# kitchenClock_v3.net
KiCad netlist of a schematic drawn in EAGLE
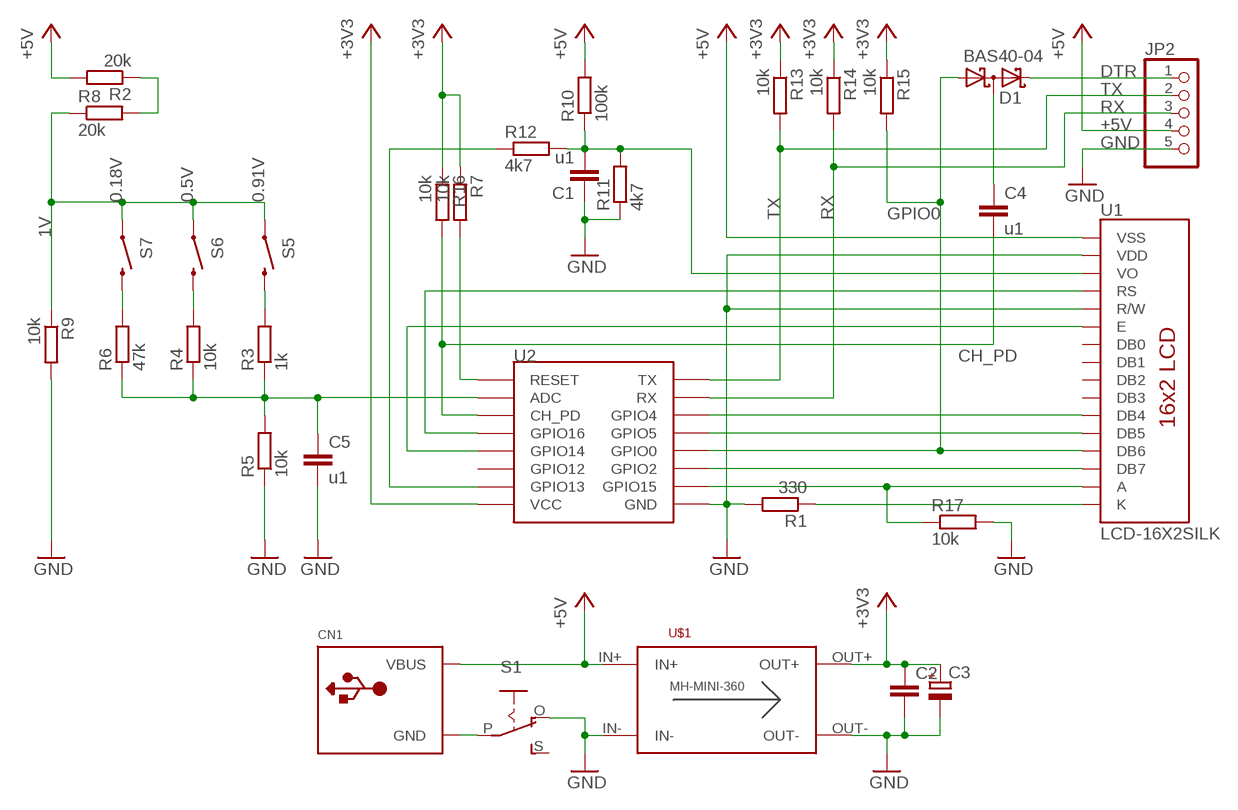
[diagram p0: schematic, sheet 1]

(export (version "E")
  (design (tool "Eeschema 10.0.6"))
  (components
    (comp (ref "C1")
      (value "u1")
      (footprint "eagle-import:C075-032X103")
      (libsource (lib "eagle-import") (part "C-EU075-032X103"))
    )
    (comp (ref "C2")
      (value "C-EU025-025X050")
      (footprint "eagle-import:C025-025X050")
      (libsource (lib "eagle-import") (part "C-EU025-025X050"))
    )
    (comp (ref "C3")
      (value "CPOL-EUTT2D5L")
      (footprint "eagle-import:TT2D5L")
      (libsource (lib "eagle-import") (part "CPOL-EUTT2D5L"))
    )
    (comp (ref "C4")
      (value "u1")
      (footprint "eagle-import:C075-032X103")
      (libsource (lib "eagle-import") (part "C-EU075-032X103"))
    )
    (comp (ref "C5")
      (value "u1")
      (footprint "eagle-import:C025-025X050")
      (libsource (lib "eagle-import") (part "C-EU025-025X050"))
    )
    (comp (ref "CN1")
      (value "USBPWR-ONLY")
      (footprint "eagle-import:USB-MINIB-THM")
      (libsource (lib "eagle-import") (part "USBPWR-ONLY"))
    )
    (comp (ref "D1")
      (value "BAS40-04")
      (footprint "eagle-import:SOT23")
      (libsource (lib "eagle-import") (part "BAS40-04"))
    )
    (comp (ref "JP2")
      (value "PINHD-1X5/90")
      (footprint "eagle-import:1X05_90")
      (libsource (lib "eagle-import") (part "PINHD-1X5/90"))
    )
    (comp (ref "R1")
      (value "330")
      (footprint "eagle-import:M0805")
      (libsource (lib "eagle-import") (part "R-EU_M0805"))
    )
    (comp (ref "R2")
      (value "20k")
      (footprint "eagle-import:0204_7")
      (libsource (lib "eagle-import") (part "R-EU_0204/7"))
    )
    (comp (ref "R3")
      (value "1k")
      (footprint "eagle-import:0204_7")
      (libsource (lib "eagle-import") (part "R-EU_0204/7"))
    )
    (comp (ref "R4")
      (value "10k")
      (footprint "eagle-import:0204_7")
      (libsource (lib "eagle-import") (part "R-EU_0204/7"))
    )
    (comp (ref "R5")
      (value "10k")
      (footprint "eagle-import:0204_7")
      (libsource (lib "eagle-import") (part "R-EU_0204/7"))
    )
    (comp (ref "R6")
      (value "47k")
      (footprint "eagle-import:0204_7")
      (libsource (lib "eagle-import") (part "R-EU_0204/7"))
    )
    (comp (ref "R7")
      (value "10k")
      (footprint "eagle-import:0204_7")
      (libsource (lib "eagle-import") (part "R-EU_0204/7"))
    )
    (comp (ref "R8")
      (value "20k")
      (footprint "eagle-import:0204_7")
      (libsource (lib "eagle-import") (part "R-EU_0204/7"))
    )
    (comp (ref "R9")
      (value "10k")
      (footprint "eagle-import:0204_7")
      (libsource (lib "eagle-import") (part "R-EU_0204/7"))
    )
    (comp (ref "R10")
      (value "100k")
      (footprint "eagle-import:M0805")
      (libsource (lib "eagle-import") (part "R-EU_M0805"))
    )
    (comp (ref "R11")
      (value "4k7")
      (footprint "eagle-import:0204_7")
      (libsource (lib "eagle-import") (part "R-EU_0204/7"))
    )
    (comp (ref "R12")
      (value "4k7")
      (footprint "eagle-import:0207_10")
      (libsource (lib "eagle-import") (part "R-EU_0207/10"))
    )
    (comp (ref "R13")
      (value "10k")
      (footprint "eagle-import:0207_10")
      (libsource (lib "eagle-import") (part "R-EU_0207/10"))
    )
    (comp (ref "R14")
      (value "10k")
      (footprint "eagle-import:0207_10")
      (libsource (lib "eagle-import") (part "R-EU_0207/10"))
    )
    (comp (ref "R15")
      (value "10k")
      (footprint "eagle-import:0207_10")
      (libsource (lib "eagle-import") (part "R-EU_0207/10"))
    )
    (comp (ref "R16")
      (value "10k")
      (footprint "eagle-import:M0805")
      (libsource (lib "eagle-import") (part "R-EU_M0805"))
    )
    (comp (ref "R17")
      (value "10k")
      (footprint "eagle-import:M0805")
      (libsource (lib "eagle-import") (part "R-EU_M0805"))
    )
    (comp (ref "S1")
      (value "EG1218S")
      (footprint "eagle-import:EG1218")
      (libsource (lib "eagle-import") (part "EG1218S"))
    )
    (comp (ref "S5")
      (value "SWITCH-MOMENTARY-2SIDE_EZ")
      (footprint "eagle-import:TACTILE-PTH-SIDEEZ")
      (libsource (lib "eagle-import") (part "SWITCH-MOMENTARY-2SIDE_EZ"))
    )
    (comp (ref "S6")
      (value "SWITCH-MOMENTARY-2SIDE_EZ")
      (footprint "eagle-import:TACTILE-PTH-SIDEEZ")
      (libsource (lib "eagle-import") (part "SWITCH-MOMENTARY-2SIDE_EZ"))
    )
    (comp (ref "S7")
      (value "SWITCH-MOMENTARY-2SIDE_EZ")
      (footprint "eagle-import:TACTILE-PTH-SIDEEZ")
      (libsource (lib "eagle-import") (part "SWITCH-MOMENTARY-2SIDE_EZ"))
    )
    (comp (ref "U$1")
      (value "DC-DC_CONV_MINISTD")
      (footprint "eagle-import:DC-DC_CONV_MINI")
      (libsource (lib "eagle-import") (part "DC-DC_CONV_MINISTD"))
    )
    (comp (ref "U1")
      (value "LCD-16X2SILK")
      (footprint "eagle-import:LCD-16X2")
      (libsource (lib "eagle-import") (part "LCD-16X2SILK"))
    )
    (comp (ref "U2")
      (value "ESP12EDIP")
      (footprint "eagle-import:ESP-12-BREAKOUT")
      (libsource (lib "eagle-import") (part "ESP12EDIP"))
    )
  )
  (nets
    (net (code "1") (name "+3V3") (class "Default")
      (node (ref "C2") (pin "1") (pinfunction "1_1") (pintype "passive"))
      (node (ref "C3") (pin "+") (pinfunction "+_+") (pintype "passive"))
      (node (ref "R13") (pin "1") (pinfunction "1_1") (pintype "passive"))
      (node (ref "R14") (pin "1") (pinfunction "1_1") (pintype "passive"))
      (node (ref "R15") (pin "1") (pinfunction "1_1") (pintype "passive"))
      (node (ref "R16") (pin "1") (pinfunction "1_1") (pintype "passive"))
      (node (ref "R7") (pin "1") (pinfunction "1_1") (pintype "passive"))
      (node (ref "U$1") (pin "OUT+") (pinfunction "OUT+_OUT+") (pintype "bidirectional"))
      (node (ref "U2") (pin "P$1") (pinfunction "VCC_P$1") (pintype "bidirectional"))
    )
    (net (code "2") (name "+5V") (class "Default")
      (node (ref "CN1") (pin "VBUS") (pinfunction "VBUS_VBUS") (pintype "power_in"))
      (node (ref "JP2") (pin "4") (pinfunction "4_4") (pintype "passive"))
      (node (ref "R10") (pin "2") (pinfunction "2_2") (pintype "passive"))
      (node (ref "R2") (pin "2") (pinfunction "2_2") (pintype "passive"))
      (node (ref "U$1") (pin "IN+") (pinfunction "IN+_IN+") (pintype "bidirectional"))
      (node (ref "U1") (pin "1") (pinfunction "VSS_1") (pintype "power_in"))
    )
    (net (code "3") (name "/1V") (class "Default")
      (node (ref "R8") (pin "1") (pinfunction "1_1") (pintype "passive"))
      (node (ref "R9") (pin "1") (pinfunction "1_1") (pintype "passive"))
      (node (ref "S5") (pin "1") (pinfunction "1_1") (pintype "passive"))
      (node (ref "S6") (pin "1") (pinfunction "1_1") (pintype "passive"))
      (node (ref "S7") (pin "1") (pinfunction "1_1") (pintype "passive"))
    )
    (net (code "4") (name "/CH_PD") (class "Default")
      (node (ref "C4") (pin "2") (pinfunction "2_2") (pintype "passive"))
      (node (ref "R16") (pin "2") (pinfunction "2_2") (pintype "passive"))
      (node (ref "U2") (pin "P$6") (pinfunction "CH_PD_P$6") (pintype "bidirectional"))
    )
    (net (code "5") (name "/DTR") (class "Default")
      (node (ref "D1") (pin "2") (pinfunction "C2_2") (pintype "passive"))
      (node (ref "JP2") (pin "1") (pinfunction "1_1") (pintype "passive"))
    )
    (net (code "6") (name "/GPIO0") (class "Default")
      (node (ref "D1") (pin "1") (pinfunction "A1_1") (pintype "passive"))
      (node (ref "R15") (pin "2") (pinfunction "2_2") (pintype "passive"))
      (node (ref "U1") (pin "13") (pinfunction "DB6_13") (pintype "bidirectional"))
      (node (ref "U2") (pin "P$12") (pinfunction "GPIO0_P$12") (pintype "bidirectional"))
    )
    (net (code "7") (name "/RX") (class "Default")
      (node (ref "JP2") (pin "3") (pinfunction "3_3") (pintype "passive"))
      (node (ref "R14") (pin "2") (pinfunction "2_2") (pintype "passive"))
      (node (ref "U2") (pin "P$15") (pinfunction "RX_P$15") (pintype "bidirectional"))
    )
    (net (code "8") (name "/TX") (class "Default")
      (node (ref "JP2") (pin "2") (pinfunction "2_2") (pintype "passive"))
      (node (ref "R13") (pin "2") (pinfunction "2_2") (pintype "passive"))
      (node (ref "U2") (pin "P$16") (pinfunction "TX_P$16") (pintype "bidirectional"))
    )
    (net (code "9") (name "GND") (class "Default")
      (node (ref "C1") (pin "1") (pinfunction "1_1") (pintype "passive"))
      (node (ref "C2") (pin "2") (pinfunction "2_2") (pintype "passive"))
      (node (ref "C3") (pin "-") (pinfunction "-_-") (pintype "passive"))
      (node (ref "C5") (pin "2") (pinfunction "2_2") (pintype "passive"))
      (node (ref "JP2") (pin "5") (pinfunction "5_5") (pintype "passive"))
      (node (ref "R1") (pin "2") (pinfunction "2_2") (pintype "passive"))
      (node (ref "R11") (pin "1") (pinfunction "1_1") (pintype "passive"))
      (node (ref "R17") (pin "2") (pinfunction "2_2") (pintype "passive"))
      (node (ref "R5") (pin "1") (pinfunction "1_1") (pintype "passive"))
      (node (ref "R9") (pin "2") (pinfunction "2_2") (pintype "passive"))
      (node (ref "S1") (pin "O") (pinfunction "O_O") (pintype "passive"))
      (node (ref "U$1") (pin "IN-") (pinfunction "IN-_IN-") (pintype "bidirectional"))
      (node (ref "U$1") (pin "OUT-") (pinfunction "OUT-_OUT-") (pintype "bidirectional"))
      (node (ref "U1") (pin "2") (pinfunction "VDD_2") (pintype "power_in"))
      (node (ref "U1") (pin "5") (pinfunction "R/W_5") (pintype "input"))
      (node (ref "U2") (pin "P$9") (pinfunction "GND_P$9") (pintype "bidirectional"))
    )
    (net (code "10") (name "Net-(CN1-GND-PadGND1)") (class "Default")
      (node (ref "CN1") (pin "GND") (pinfunction "GND_GND") (pintype "power_in"))
      (node (ref "CN1") (pin "GND1") (pinfunction "GND_GND1") (pintype "power_in"))
      (node (ref "CN1") (pin "GND2") (pinfunction "GND_GND2") (pintype "power_in"))
      (node (ref "CN1") (pin "GND3") (pinfunction "GND_GND3") (pintype "power_in"))
      (node (ref "CN1") (pin "GND4") (pinfunction "GND_GND4") (pintype "power_in"))
      (node (ref "S1") (pin "P") (pinfunction "P_P") (pintype "passive"))
    )
    (net (code "11") (name "Net-(D1-C1A2)") (class "Default")
      (node (ref "C4") (pin "1") (pinfunction "1_1") (pintype "passive"))
      (node (ref "D1") (pin "3") (pinfunction "C1A2_3") (pintype "passive"))
    )
    (net (code "12") (name "Net-(R2-Pad1)") (class "Default")
      (node (ref "R2") (pin "1") (pinfunction "1_1") (pintype "passive"))
      (node (ref "R8") (pin "2") (pinfunction "2_2") (pintype "passive"))
    )
    (net (code "13") (name "Net-(R3-Pad2)") (class "Default")
      (node (ref "R3") (pin "2") (pinfunction "2_2") (pintype "passive"))
      (node (ref "S5") (pin "2") (pinfunction "2_2") (pintype "passive"))
    )
    (net (code "14") (name "Net-(R4-Pad2)") (class "Default")
      (node (ref "R4") (pin "2") (pinfunction "2_2") (pintype "passive"))
      (node (ref "S6") (pin "2") (pinfunction "2_2") (pintype "passive"))
    )
    (net (code "15") (name "Net-(R6-Pad2)") (class "Default")
      (node (ref "R6") (pin "2") (pinfunction "2_2") (pintype "passive"))
      (node (ref "S7") (pin "2") (pinfunction "2_2") (pintype "passive"))
    )
    (net (code "16") (name "Net-(U1-A)") (class "Default")
      (node (ref "R17") (pin "1") (pinfunction "1_1") (pintype "passive"))
      (node (ref "U1") (pin "15") (pinfunction "A_15") (pintype "power_in"))
      (node (ref "U2") (pin "P$10") (pinfunction "GPIO15_P$10") (pintype "bidirectional"))
    )
    (net (code "17") (name "Net-(U1-DB4)") (class "Default")
      (node (ref "U1") (pin "11") (pinfunction "DB4_11") (pintype "bidirectional"))
      (node (ref "U2") (pin "P$14") (pinfunction "GPIO4_P$14") (pintype "bidirectional"))
    )
    (net (code "18") (name "Net-(U1-DB5)") (class "Default")
      (node (ref "U1") (pin "12") (pinfunction "DB5_12") (pintype "bidirectional"))
      (node (ref "U2") (pin "P$13") (pinfunction "GPIO5_P$13") (pintype "bidirectional"))
    )
    (net (code "19") (name "Net-(U1-DB7)") (class "Default")
      (node (ref "U1") (pin "14") (pinfunction "DB7_14") (pintype "bidirectional"))
      (node (ref "U2") (pin "P$11") (pinfunction "GPIO2_P$11") (pintype "bidirectional"))
    )
    (net (code "20") (name "Net-(U1-E)") (class "Default")
      (node (ref "U1") (pin "6") (pinfunction "E_6") (pintype "input"))
      (node (ref "U2") (pin "P$4") (pinfunction "GPIO14_P$4") (pintype "bidirectional"))
    )
    (net (code "21") (name "Net-(U1-K)") (class "Default")
      (node (ref "R1") (pin "1") (pinfunction "1_1") (pintype "passive"))
      (node (ref "U1") (pin "16") (pinfunction "K_16") (pintype "power_in"))
    )
    (net (code "22") (name "Net-(U1-RS)") (class "Default")
      (node (ref "U1") (pin "4") (pinfunction "RS_4") (pintype "input"))
      (node (ref "U2") (pin "P$5") (pinfunction "GPIO16_P$5") (pintype "bidirectional"))
    )
    (net (code "23") (name "Net-(U1-VO)") (class "Default")
      (node (ref "C1") (pin "2") (pinfunction "2_2") (pintype "passive"))
      (node (ref "R10") (pin "1") (pinfunction "1_1") (pintype "passive"))
      (node (ref "R11") (pin "2") (pinfunction "2_2") (pintype "passive"))
      (node (ref "R12") (pin "2") (pinfunction "2_2") (pintype "passive"))
      (node (ref "U1") (pin "3") (pinfunction "VO_3") (pintype "bidirectional"))
    )
    (net (code "24") (name "Net-(U2-ADC)") (class "Default")
      (node (ref "C5") (pin "1") (pinfunction "1_1") (pintype "passive"))
      (node (ref "R3") (pin "1") (pinfunction "1_1") (pintype "passive"))
      (node (ref "R4") (pin "1") (pinfunction "1_1") (pintype "passive"))
      (node (ref "R5") (pin "2") (pinfunction "2_2") (pintype "passive"))
      (node (ref "R6") (pin "1") (pinfunction "1_1") (pintype "passive"))
      (node (ref "U2") (pin "P$7") (pinfunction "ADC_P$7") (pintype "bidirectional"))
    )
    (net (code "25") (name "Net-(U2-GPIO13)") (class "Default")
      (node (ref "R12") (pin "1") (pinfunction "1_1") (pintype "passive"))
      (node (ref "U2") (pin "P$2") (pinfunction "GPIO13_P$2") (pintype "bidirectional"))
    )
    (net (code "26") (name "Net-(U2-RESET)") (class "Default")
      (node (ref "R7") (pin "2") (pinfunction "2_2") (pintype "passive"))
      (node (ref "U2") (pin "P$8") (pinfunction "RESET_P$8") (pintype "bidirectional"))
    )
    (net (code "27") (name "unconnected-(S1-PadS)") (class "Default")
      (node (ref "S1") (pin "S") (pinfunction "S_S") (pintype "passive"))
    )
    (net (code "28") (name "unconnected-(U1-DB0-Pad7)") (class "Default")
      (node (ref "U1") (pin "7") (pinfunction "DB0_7") (pintype "bidirectional"))
    )
    (net (code "29") (name "unconnected-(U1-DB1-Pad8)") (class "Default")
      (node (ref "U1") (pin "8") (pinfunction "DB1_8") (pintype "bidirectional"))
    )
    (net (code "30") (name "unconnected-(U1-DB2-Pad9)") (class "Default")
      (node (ref "U1") (pin "9") (pinfunction "DB2_9") (pintype "bidirectional"))
    )
    (net (code "31") (name "unconnected-(U1-DB3-Pad10)") (class "Default")
      (node (ref "U1") (pin "10") (pinfunction "DB3_10") (pintype "bidirectional"))
    )
    (net (code "32") (name "unconnected-(U2-GPIO12-PadP$3)") (class "Default")
      (node (ref "U2") (pin "P$3") (pinfunction "GPIO12_P$3") (pintype "bidirectional"))
    )
  )
)
